# Power.net
KiCad netlist of a schematic drawn in Altium Designer
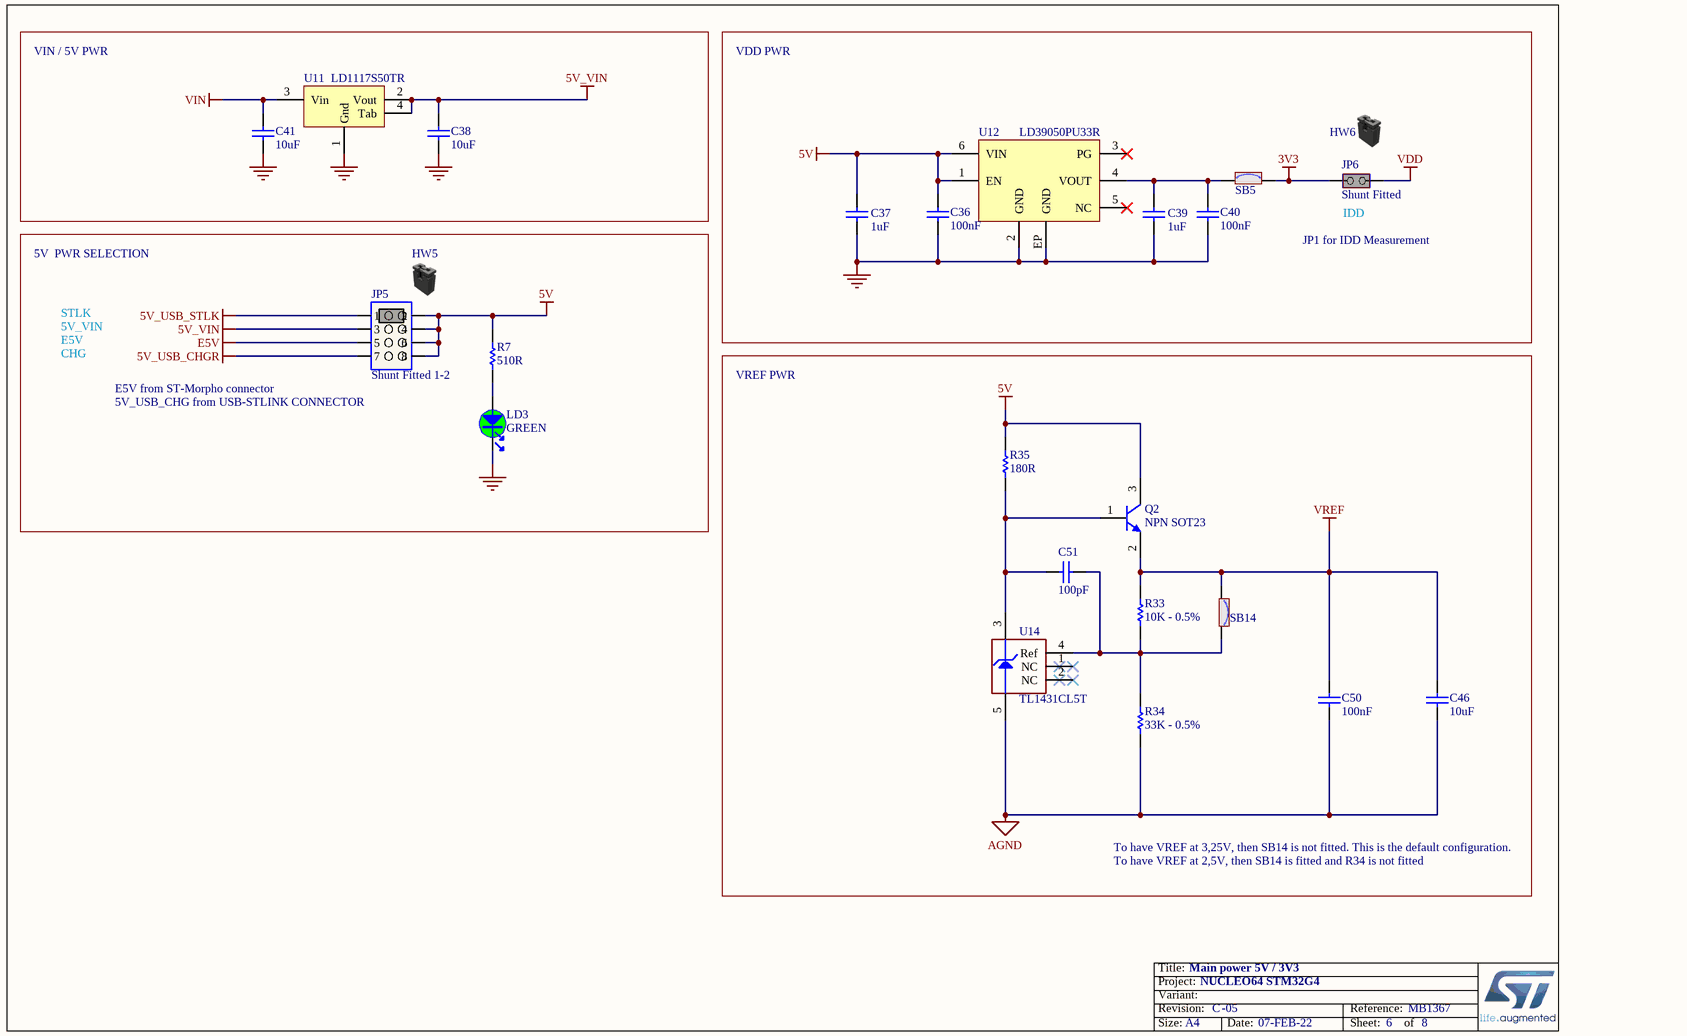
[diagram p0: Power.SchDoc]

(export (version "E")
  (design (tool "Eeschema 10.0.6"))
  (components
    (comp (ref "C36")
      (value "100nF")
      (footprint "C0402")
      (description "Capacitor, MLCC, 100nF, 16V, X7R, 10%, 0402, T=0,5mm")
      (fields
        (field (name "INTERNAL_PART_NUMBER") "MCD-00102")
        (field (name "MANUFACTURER_PART_NUMBER") "CC0402KRX7R7BB104")
        (field (name "PROVIDED_BY") "Subcon")
      )
      (libsource (lib "MCD_PARTS_database") (part "Capacitor"))
    )
    (comp (ref "C37")
      (value "1uF")
      (footprint "C0603")
      (description "Capacitor, MLCC, 1uF, 16V, X5R, 10%, 0603, T=0,8mm")
      (fields
        (field (name "INTERNAL_PART_NUMBER") "MCD-00010")
        (field (name "MANUFACTURER_PART_NUMBER") "CC0603KRX5R7BB105")
        (field (name "PROVIDED_BY") "Subcon")
      )
      (libsource (lib "MCD_PARTS_database") (part "Capacitor"))
    )
    (comp (ref "C38")
      (value "10uF")
      (footprint "C0805")
      (description "Capacitor, MLCC, 10uF, 25V, X5R, 10%, 0805, T=0,85mm")
      (fields
        (field (name "INTERNAL_PART_NUMBER") "MCD-00014")
        (field (name "MANUFACTURER_PART_NUMBER") "CC0805KRX5R8BB106")
        (field (name "PROVIDED_BY") "SUBCO")
      )
      (libsource (lib "MCD_PARTS_database") (part "Capacitor"))
    )
    (comp (ref "C39")
      (value "1uF")
      (footprint "C0603")
      (description "Capacitor, MLCC, 1uF, 16V, X5R, 10%, 0603, T=0,8mm")
      (fields
        (field (name "INTERNAL_PART_NUMBER") "MCD-00010")
        (field (name "MANUFACTURER_PART_NUMBER") "CC0603KRX5R7BB105")
        (field (name "PROVIDED_BY") "Subcon")
      )
      (libsource (lib "MCD_PARTS_database") (part "Capacitor"))
    )
    (comp (ref "C40")
      (value "100nF")
      (footprint "C0402")
      (description "Capacitor, MLCC, 100nF, 16V, X7R, 10%, 0402, T=0,5mm")
      (fields
        (field (name "INTERNAL_PART_NUMBER") "MCD-00102")
        (field (name "MANUFACTURER_PART_NUMBER") "CC0402KRX7R7BB104")
        (field (name "PROVIDED_BY") "Subcon")
      )
      (libsource (lib "MCD_PARTS_database") (part "Capacitor"))
    )
    (comp (ref "C41")
      (value "10uF")
      (footprint "C0805")
      (description "Capacitor, MLCC, 10uF, 25V, X5R, 10%, 0805, T=0,85mm")
      (fields
        (field (name "INTERNAL_PART_NUMBER") "MCD-00014")
        (field (name "MANUFACTURER_PART_NUMBER") "CC0805KRX5R8BB106")
        (field (name "PROVIDED_BY") "SUBCO")
      )
      (libsource (lib "MCD_PARTS_database") (part "Capacitor"))
    )
    (comp (ref "C46")
      (value "10uF")
      (footprint "C0603")
      (description "Capacitor, MLCC, 10uF, 10V, X5R, 10%, 0603, T=0.8mm")
      (fields
        (field (name "INTERNAL_PART_NUMBER") "MCD-01124")
        (field (name "MANUFACTURER_PART_NUMBER") "GRM188R61A106KAAL")
        (field (name "PROVIDED_BY") "SUBCO")
      )
      (libsource (lib "MCD_PARTS_database") (part "Capacitor"))
    )
    (comp (ref "C50")
      (value "100nF")
      (footprint "C0603")
      (description "Capacitor, MLCC, 100nF, 16V, X7R, 10%, 0603, T=0,8mm")
      (fields
        (field (name "INTERNAL_PART_NUMBER") "MCD-00211")
        (field (name "MANUFACTURER_PART_NUMBER") "CC0603KRX7R7BB104")
        (field (name "PROVIDED_BY") "SUBCO")
      )
      (libsource (lib "MCD_PARTS_database") (part "Capacitor"))
    )
    (comp (ref "C51")
      (value "100pF")
      (footprint "C0603")
      (description "Capacitor,100pF,50V,X7R,10%,0603")
      (fields
        (field (name "INTERNAL_PART_NUMBER") "MCD-01101")
        (field (name "MANUFACTURER_PART_NUMBER") "06035C101JAT4A")
        (field (name "PROVIDED_BY") "SUBCO")
      )
      (libsource (lib "MCD_PARTS_database") (part "Capacitor"))
    )
    (comp (ref "HW5")
      (value "~")
      (description "SHUNT 2.54mm BLACK")
      (fields
        (field (name "INTERNAL_PART_NUMBER") "MCD-00043")
        (field (name "MANUFACTURER_PART_NUMBER") "SNT-100-BK-G")
        (field (name "PROVIDED_BY") "Subcon")
      )
      (libsource (lib "MCD_PARTS_database") (part "Shunt Black 2.54mm"))
    )
    (comp (ref "HW6")
      (value "~")
      (description "SHUNT 2.54mm BLACK")
      (fields
        (field (name "INTERNAL_PART_NUMBER") "MCD-00043")
        (field (name "MANUFACTURER_PART_NUMBER") "SNT-100-BK-G")
        (field (name "PROVIDED_BY") "Subcon")
      )
      (libsource (lib "MCD_PARTS_database") (part "Shunt Black 2.54mm"))
    )
    (comp (ref "JP5")
      (value "Shunt Fitted 1-2")
      (footprint "CON_SAMTEC_TSW-104-07-X-D")
      (description "Header, 4x2, 2,54mm, VR, TH, Height 5.84mm/2.54mm - Shunt Fitted 1-2")
      (fields
        (field (name "INTERNAL_PART_NUMBER") "MCD-00686")
        (field (name "MANUFACTURER_PART_NUMBER") "TSW-104-07-x-D")
        (field (name "PROVIDED_BY") "SUBCO")
      )
      (libsource (lib "MCD_PARTS_database") (part "Jumper_Header 4x2 Fitted 1-2"))
    )
    (comp (ref "JP6")
      (value "Shunt Fitted")
      (footprint "CON_SAMTEC_TSW-102-07-G-S")
      (description "Header, 2x1, 2,54mm, VR, TH, Height 5.84mm/2.54mm - Shunt Fitted by default")
      (fields
        (field (name "INTERNAL_PART_NUMBER") "MCD-00683")
        (field (name "MANUFACTURER_PART_NUMBER") "TSW-102-07-x-S")
        (field (name "PROVIDED_BY") "Subcon")
      )
      (libsource (lib "MCD_PARTS_database") (part "Jumper_Header 2x1 Fitted"))
    )
    (comp (ref "LD3")
      (value "GREEN")
      (footprint "LED_0603_GREEN")
      (description "LED, GREEN, 0603, VF : 2.4V max ; IF: 20mA")
      (fields
        (field (name "INTERNAL_PART_NUMBER") "MCD-02520")
        (field (name "MANUFACTURER") "OSRAM OPTO SEMICONDUCTORS")
      )
      (libsource (lib "MCD_PARTS_database") (part "LED_green"))
    )
    (comp (ref "Q2")
      (value "NPN SOT23")
      (footprint "NPN_SOT23")
      (description "NPN Bipolar Transistor")
      (fields
        (field (name "INTERNAL_PART_NUMBER") "MCD-00073")
        (field (name "MANUFACTURER_PART_NUMBER") "BSR14")
        (field (name "PROVIDED_BY") "SUBCO")
      )
      (libsource (lib "MCD_PARTS_database") (part "9013-SOT23"))
    )
    (comp (ref "R7")
      (value "510R")
      (footprint "R0603")
      (description "Resistor,510R,0603,1%,1/10W")
      (fields
        (field (name "INTERNAL_PART_NUMBER") "MCD-00225")
        (field (name "MANUFACTURER_PART_NUMBER") "RC0603FR-07510RL")
        (field (name "PROVIDED_BY") "SUBCO")
      )
      (libsource (lib "MCD_PARTS_database") (part "Resistor"))
    )
    (comp (ref "R33")
      (value "10K - 0.5%")
      (footprint "R0603")
      (description "resistor, 10K, 0603, 0.5%, 1/10W")
      (fields
        (field (name "INTERNAL_PART_NUMBER") "MCD-01215")
        (field (name "MANUFACTURER_PART_NUMBER") "RC0603DR-0710KL")
        (field (name "PROVIDED_BY") "SUBCO")
      )
      (libsource (lib "MCD_PARTS_database") (part "Resistor"))
    )
    (comp (ref "R34")
      (value "33K - 0.5%")
      (footprint "R0603")
      (description "Resistor,33K,0603,0.5%,1/10W")
      (fields
        (field (name "INTERNAL_PART_NUMBER") "MCD-01209")
        (field (name "MANUFACTURER_PART_NUMBER") "RC0603DR-0733KL")
        (field (name "PROVIDED_BY") "SUBCO")
      )
      (libsource (lib "MCD_PARTS_database") (part "Resistor"))
    )
    (comp (ref "R35")
      (value "180R")
      (footprint "R0603")
      (description "Resistor,180R,0603,1%,1/10W")
      (fields
        (field (name "INTERNAL_PART_NUMBER") "MCD-00342")
        (field (name "MANUFACTURER_PART_NUMBER") "RC0603FR-07180RL")
        (field (name "PROVIDED_BY") "SUBCO")
      )
      (libsource (lib "MCD_PARTS_database") (part "Resistor"))
    )
    (comp (ref "SB5")
      (value "~")
      (footprint "SOLDER-BRIDGE_R0603-0R")
      (description "Solder Bridge ON")
      (fields
        (field (name "INTERNAL_PART_NUMBER") "MCD-00071")
        (field (name "MANUFACTURER_PART_NUMBER") "RC0603JR-070RL")
        (field (name "PROVIDED_BY") "SUBCO")
      )
      (libsource (lib "") (part "SB_ON_1"))
    )
    (comp (ref "SB14")
      (value "~")
      (footprint "SOLDER-BRIDGE_R0603-0R")
      (description "Solder Bridge ON")
      (fields
        (field (name "INTERNAL_PART_NUMBER") "MCD-00071")
        (field (name "MANUFACTURER_PART_NUMBER") "RC0603JR-070RL")
        (field (name "PROVIDED_BY") "SUBCO")
      )
      (libsource (lib "MCD_PARTS_database") (part "SB_ON"))
    )
    (comp (ref "U11")
      (value "LD1117S50TR")
      (footprint "REG_SOT223-TAB")
      (description "IC REG LDO 5V 0.8A SOT223")
      (fields
        (field (name "INTERNAL_PART_NUMBER") "MCD-00088")
        (field (name "MANUFACTURER") "STMICROELECTRONICS")
        (field (name "PROVIDED_BY") "SUBCO with ST control")
      )
      (libsource (lib "MCD_PARTS_database") (part "LD1117S50TR"))
    )
    (comp (ref "U12")
      (value "LD39050PU33R")
      (footprint "ICC_DFN6-EPAD_3X3_P095")
      (description "Low quiescent current and low noise voltage regulators")
      (fields
        (field (name "INTERNAL_PART_NUMBER") "MCD-00215")
        (field (name "MANUFACTURER") "STMICROELECTRONICS")
        (field (name "PROVIDED_BY") "SUBCO with ST control")
      )
      (libsource (lib "MCD_PARTS_database") (part "LD39050PU33R"))
    )
    (comp (ref "U14")
      (value "TL1431CL5T")
      (footprint "ICC_SOT23-5L_H1P45")
      (description "Programmable voltage reference with 0.4% voltage precision")
      (fields
        (field (name "INTERNAL_PART_NUMBER") "MCD-01802")
        (field (name "MANUFACTURER") "STMICROELECTRONICS")
        (field (name "PROVIDED_BY") "SUBCO with ST control")
      )
      (libsource (lib "MCD_PARTS_database") (part "TL1431ACL5T"))
    )
  )
  (nets
    (net (code "1") (name "3V3") (class "Default")
      (node (ref "JP6") (pin "1") (pinfunction "COMMON_1") (pintype "passive"))
      (node (ref "SB5") (pin "2") (pinfunction "2_2") (pintype "passive"))
    )
    (net (code "2") (name "5V") (class "Default")
      (node (ref "C36") (pin "2") (pinfunction "2_2") (pintype "passive"))
      (node (ref "C37") (pin "2") (pinfunction "2_2") (pintype "passive"))
      (node (ref "JP5") (pin "2") (pinfunction "2_2") (pintype "passive"))
      (node (ref "JP5") (pin "4") (pinfunction "4_4") (pintype "passive"))
      (node (ref "JP5") (pin "6") (pinfunction "6_6") (pintype "passive"))
      (node (ref "JP5") (pin "8") (pinfunction "8_8") (pintype "passive"))
      (node (ref "Q2") (pin "3") (pinfunction "C_3") (pintype "passive"))
      (node (ref "R35") (pin "2") (pinfunction "2_2") (pintype "passive"))
      (node (ref "R7") (pin "2") (pinfunction "2_2") (pintype "passive"))
      (node (ref "U12") (pin "1") (pinfunction "EN_1") (pintype "passive"))
      (node (ref "U12") (pin "6") (pinfunction "VIN_6") (pintype "passive"))
    )
    (net (code "3") (name "5V_USB_CHGR") (class "Default")
      (node (ref "JP5") (pin "7") (pinfunction "7_7") (pintype "passive"))
    )
    (net (code "4") (name "5V_USB_STLK") (class "Default")
      (node (ref "JP5") (pin "1") (pinfunction "1_1") (pintype "passive"))
    )
    (net (code "5") (name "5V_VIN") (class "Default")
      (node (ref "C38") (pin "2") (pinfunction "2_2") (pintype "passive"))
      (node (ref "JP5") (pin "3") (pinfunction "3_3") (pintype "passive"))
      (node (ref "U11") (pin "2") (pinfunction "Vout_2") (pintype "passive"))
      (node (ref "U11") (pin "4") (pinfunction "Tab_4") (pintype "passive"))
    )
    (net (code "6") (name "AGND") (class "Default")
      (node (ref "C46") (pin "1") (pinfunction "1_1") (pintype "passive"))
      (node (ref "C50") (pin "1") (pinfunction "1_1") (pintype "passive"))
      (node (ref "R34") (pin "1") (pinfunction "1_1") (pintype "passive"))
      (node (ref "U14") (pin "5") (pinfunction "Anode_5") (pintype "passive"))
    )
    (net (code "7") (name "E5V") (class "Default")
      (node (ref "JP5") (pin "5") (pinfunction "5_5") (pintype "passive"))
    )
    (net (code "8") (name "GND") (class "Default")
      (node (ref "C36") (pin "1") (pinfunction "1_1") (pintype "passive"))
      (node (ref "C37") (pin "1") (pinfunction "1_1") (pintype "passive"))
      (node (ref "C38") (pin "1") (pinfunction "1_1") (pintype "passive"))
      (node (ref "C39") (pin "1") (pinfunction "1_1") (pintype "passive"))
      (node (ref "C40") (pin "1") (pinfunction "1_1") (pintype "passive"))
      (node (ref "C41") (pin "1") (pinfunction "1_1") (pintype "passive"))
      (node (ref "LD3") (pin "2") (pintype "passive"))
      (node (ref "U11") (pin "1") (pinfunction "Gnd_1") (pintype "passive"))
      (node (ref "U12") (pin "2") (pinfunction "GND_2") (pintype "passive"))
      (node (ref "U12") (pin "EP") (pinfunction "GND_EP") (pintype "passive"))
    )
    (net (code "9") (name "Net-(LD3-Pad1)") (class "Default")
      (node (ref "LD3") (pin "1") (pintype "passive"))
      (node (ref "R7") (pin "1") (pinfunction "1_1") (pintype "passive"))
    )
    (net (code "10") (name "Net-(Q2-B)") (class "Default")
      (node (ref "C51") (pin "1") (pinfunction "1_1") (pintype "passive"))
      (node (ref "Q2") (pin "1") (pinfunction "B_1") (pintype "passive"))
      (node (ref "R35") (pin "1") (pinfunction "1_1") (pintype "passive"))
      (node (ref "U14") (pin "3") (pinfunction "Cathode_3") (pintype "passive"))
    )
    (net (code "11") (name "Net-(U12-VOUT)") (class "Default")
      (node (ref "C39") (pin "2") (pinfunction "2_2") (pintype "passive"))
      (node (ref "C40") (pin "2") (pinfunction "2_2") (pintype "passive"))
      (node (ref "SB5") (pin "1") (pinfunction "1_1") (pintype "passive"))
      (node (ref "U12") (pin "4") (pinfunction "VOUT_4") (pintype "passive"))
    )
    (net (code "12") (name "Net-(U14-Ref)") (class "Default")
      (node (ref "C51") (pin "2") (pinfunction "2_2") (pintype "passive"))
      (node (ref "R33") (pin "1") (pinfunction "1_1") (pintype "passive"))
      (node (ref "R34") (pin "2") (pinfunction "2_2") (pintype "passive"))
      (node (ref "SB14") (pin "2") (pinfunction "2_2") (pintype "passive"))
      (node (ref "U14") (pin "4") (pinfunction "Ref_4") (pintype "passive"))
    )
    (net (code "13") (name "VDD") (class "Default")
      (node (ref "JP6") (pin "2") (pinfunction "NO_2") (pintype "passive"))
    )
    (net (code "14") (name "VIN") (class "Default")
      (node (ref "C41") (pin "2") (pinfunction "2_2") (pintype "passive"))
      (node (ref "U11") (pin "3") (pinfunction "Vin_3") (pintype "passive"))
    )
    (net (code "15") (name "VREF") (class "Default")
      (node (ref "C46") (pin "2") (pinfunction "2_2") (pintype "passive"))
      (node (ref "C50") (pin "2") (pinfunction "2_2") (pintype "passive"))
      (node (ref "Q2") (pin "2") (pinfunction "E_2") (pintype "passive"))
      (node (ref "R33") (pin "2") (pinfunction "2_2") (pintype "passive"))
      (node (ref "SB14") (pin "1") (pinfunction "1_1") (pintype "passive"))
    )
    (net (code "16") (name "unconnected-(U12-NC-Pad5)") (class "Default")
      (node (ref "U12") (pin "5") (pinfunction "NC_5") (pintype "passive+no_connect"))
    )
    (net (code "17") (name "unconnected-(U12-PG-Pad3)") (class "Default")
      (node (ref "U12") (pin "3") (pinfunction "PG_3") (pintype "passive+no_connect"))
    )
    (net (code "18") (name "unconnected-(U14-NC-Pad1)") (class "Default")
      (node (ref "U14") (pin "1") (pinfunction "NC_1") (pintype "passive+no_connect"))
    )
    (net (code "19") (name "unconnected-(U14-NC-Pad2)") (class "Default")
      (node (ref "U14") (pin "2") (pinfunction "NC_2") (pintype "passive+no_connect"))
    )
  )
)
